# proto-small.net
KiCad netlist of a schematic drawn in EAGLE
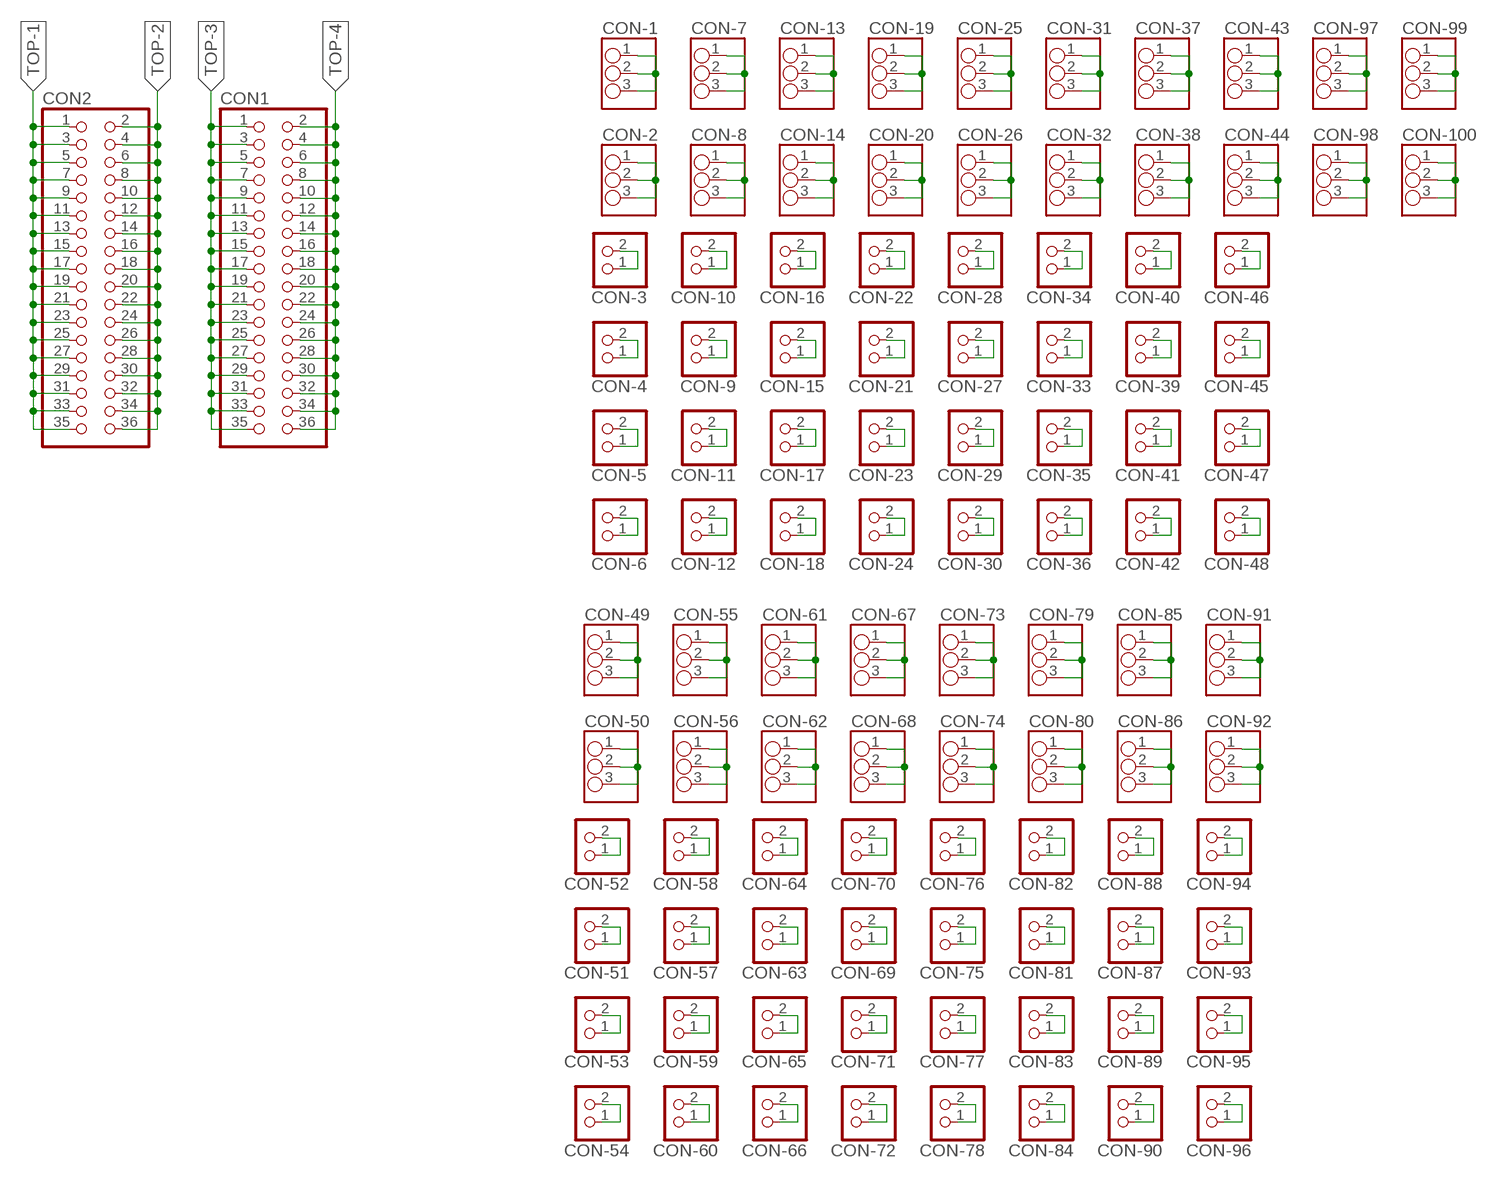
[diagram p0: schematic, sheet 1]

(export (version "E")
  (design (tool "Eeschema 10.0.6"))
  (components
    (comp (ref "CON-1")
      (value "GENERIC-1X3")
      (footprint "eagle-import:PINHEADER-100MIL-1X3-NOSILK")
      (libsource (lib "eagle-import") (part "GENERIC-1X3"))
    )
    (comp (ref "CON-2")
      (value "GENERIC-1X3")
      (footprint "eagle-import:PINHEADER-100MIL-1X3-NOSILK")
      (libsource (lib "eagle-import") (part "GENERIC-1X3"))
    )
    (comp (ref "CON-3")
      (value "GENERIC-1X2")
      (footprint "eagle-import:PINHEADER-100MIL-1X2-NOSILK")
      (libsource (lib "eagle-import") (part "GENERIC-1X2"))
    )
    (comp (ref "CON-4")
      (value "GENERIC-1X2")
      (footprint "eagle-import:PINHEADER-100MIL-1X2-NOSILK")
      (libsource (lib "eagle-import") (part "GENERIC-1X2"))
    )
    (comp (ref "CON-5")
      (value "GENERIC-1X2")
      (footprint "eagle-import:PINHEADER-100MIL-1X2-NOSILK")
      (libsource (lib "eagle-import") (part "GENERIC-1X2"))
    )
    (comp (ref "CON-6")
      (value "GENERIC-1X2")
      (footprint "eagle-import:PINHEADER-100MIL-1X2-NOSILK")
      (libsource (lib "eagle-import") (part "GENERIC-1X2"))
    )
    (comp (ref "CON-7")
      (value "GENERIC-1X3")
      (footprint "eagle-import:PINHEADER-100MIL-1X3-NOSILK")
      (libsource (lib "eagle-import") (part "GENERIC-1X3"))
    )
    (comp (ref "CON-8")
      (value "GENERIC-1X3")
      (footprint "eagle-import:PINHEADER-100MIL-1X3-NOSILK")
      (libsource (lib "eagle-import") (part "GENERIC-1X3"))
    )
    (comp (ref "CON-9")
      (value "GENERIC-1X2")
      (footprint "eagle-import:PINHEADER-100MIL-1X2-NOSILK")
      (libsource (lib "eagle-import") (part "GENERIC-1X2"))
    )
    (comp (ref "CON-10")
      (value "GENERIC-1X2")
      (footprint "eagle-import:PINHEADER-100MIL-1X2-NOSILK")
      (libsource (lib "eagle-import") (part "GENERIC-1X2"))
    )
    (comp (ref "CON-11")
      (value "GENERIC-1X2")
      (footprint "eagle-import:PINHEADER-100MIL-1X2-NOSILK")
      (libsource (lib "eagle-import") (part "GENERIC-1X2"))
    )
    (comp (ref "CON-12")
      (value "GENERIC-1X2")
      (footprint "eagle-import:PINHEADER-100MIL-1X2-NOSILK")
      (libsource (lib "eagle-import") (part "GENERIC-1X2"))
    )
    (comp (ref "CON-13")
      (value "GENERIC-1X3")
      (footprint "eagle-import:PINHEADER-100MIL-1X3-NOSILK")
      (libsource (lib "eagle-import") (part "GENERIC-1X3"))
    )
    (comp (ref "CON-14")
      (value "GENERIC-1X3")
      (footprint "eagle-import:PINHEADER-100MIL-1X3-NOSILK")
      (libsource (lib "eagle-import") (part "GENERIC-1X3"))
    )
    (comp (ref "CON-15")
      (value "GENERIC-1X2")
      (footprint "eagle-import:PINHEADER-100MIL-1X2-NOSILK")
      (libsource (lib "eagle-import") (part "GENERIC-1X2"))
    )
    (comp (ref "CON-16")
      (value "GENERIC-1X2")
      (footprint "eagle-import:PINHEADER-100MIL-1X2-NOSILK")
      (libsource (lib "eagle-import") (part "GENERIC-1X2"))
    )
    (comp (ref "CON-17")
      (value "GENERIC-1X2")
      (footprint "eagle-import:PINHEADER-100MIL-1X2-NOSILK")
      (libsource (lib "eagle-import") (part "GENERIC-1X2"))
    )
    (comp (ref "CON-18")
      (value "GENERIC-1X2")
      (footprint "eagle-import:PINHEADER-100MIL-1X2-NOSILK")
      (libsource (lib "eagle-import") (part "GENERIC-1X2"))
    )
    (comp (ref "CON-19")
      (value "GENERIC-1X3")
      (footprint "eagle-import:PINHEADER-100MIL-1X3-NOSILK")
      (libsource (lib "eagle-import") (part "GENERIC-1X3"))
    )
    (comp (ref "CON-20")
      (value "GENERIC-1X3")
      (footprint "eagle-import:PINHEADER-100MIL-1X3-NOSILK")
      (libsource (lib "eagle-import") (part "GENERIC-1X3"))
    )
    (comp (ref "CON-21")
      (value "GENERIC-1X2")
      (footprint "eagle-import:PINHEADER-100MIL-1X2-NOSILK")
      (libsource (lib "eagle-import") (part "GENERIC-1X2"))
    )
    (comp (ref "CON-22")
      (value "GENERIC-1X2")
      (footprint "eagle-import:PINHEADER-100MIL-1X2-NOSILK")
      (libsource (lib "eagle-import") (part "GENERIC-1X2"))
    )
    (comp (ref "CON-23")
      (value "GENERIC-1X2")
      (footprint "eagle-import:PINHEADER-100MIL-1X2-NOSILK")
      (libsource (lib "eagle-import") (part "GENERIC-1X2"))
    )
    (comp (ref "CON-24")
      (value "GENERIC-1X2")
      (footprint "eagle-import:PINHEADER-100MIL-1X2-NOSILK")
      (libsource (lib "eagle-import") (part "GENERIC-1X2"))
    )
    (comp (ref "CON-25")
      (value "GENERIC-1X3")
      (footprint "eagle-import:PINHEADER-100MIL-1X3-NOSILK")
      (libsource (lib "eagle-import") (part "GENERIC-1X3"))
    )
    (comp (ref "CON-26")
      (value "GENERIC-1X3")
      (footprint "eagle-import:PINHEADER-100MIL-1X3-NOSILK")
      (libsource (lib "eagle-import") (part "GENERIC-1X3"))
    )
    (comp (ref "CON-27")
      (value "GENERIC-1X2")
      (footprint "eagle-import:PINHEADER-100MIL-1X2-NOSILK")
      (libsource (lib "eagle-import") (part "GENERIC-1X2"))
    )
    (comp (ref "CON-28")
      (value "GENERIC-1X2")
      (footprint "eagle-import:PINHEADER-100MIL-1X2-NOSILK")
      (libsource (lib "eagle-import") (part "GENERIC-1X2"))
    )
    (comp (ref "CON-29")
      (value "GENERIC-1X2")
      (footprint "eagle-import:PINHEADER-100MIL-1X2-NOSILK")
      (libsource (lib "eagle-import") (part "GENERIC-1X2"))
    )
    (comp (ref "CON-30")
      (value "GENERIC-1X2")
      (footprint "eagle-import:PINHEADER-100MIL-1X2-NOSILK")
      (libsource (lib "eagle-import") (part "GENERIC-1X2"))
    )
    (comp (ref "CON-31")
      (value "GENERIC-1X3")
      (footprint "eagle-import:PINHEADER-100MIL-1X3-NOSILK")
      (libsource (lib "eagle-import") (part "GENERIC-1X3"))
    )
    (comp (ref "CON-32")
      (value "GENERIC-1X3")
      (footprint "eagle-import:PINHEADER-100MIL-1X3-NOSILK")
      (libsource (lib "eagle-import") (part "GENERIC-1X3"))
    )
    (comp (ref "CON-33")
      (value "GENERIC-1X2")
      (footprint "eagle-import:PINHEADER-100MIL-1X2-NOSILK")
      (libsource (lib "eagle-import") (part "GENERIC-1X2"))
    )
    (comp (ref "CON-34")
      (value "GENERIC-1X2")
      (footprint "eagle-import:PINHEADER-100MIL-1X2-NOSILK")
      (libsource (lib "eagle-import") (part "GENERIC-1X2"))
    )
    (comp (ref "CON-35")
      (value "GENERIC-1X2")
      (footprint "eagle-import:PINHEADER-100MIL-1X2-NOSILK")
      (libsource (lib "eagle-import") (part "GENERIC-1X2"))
    )
    (comp (ref "CON-36")
      (value "GENERIC-1X2")
      (footprint "eagle-import:PINHEADER-100MIL-1X2-NOSILK")
      (libsource (lib "eagle-import") (part "GENERIC-1X2"))
    )
    (comp (ref "CON-37")
      (value "GENERIC-1X3")
      (footprint "eagle-import:PINHEADER-100MIL-1X3-NOSILK")
      (libsource (lib "eagle-import") (part "GENERIC-1X3"))
    )
    (comp (ref "CON-38")
      (value "GENERIC-1X3")
      (footprint "eagle-import:PINHEADER-100MIL-1X3-NOSILK")
      (libsource (lib "eagle-import") (part "GENERIC-1X3"))
    )
    (comp (ref "CON-39")
      (value "GENERIC-1X2")
      (footprint "eagle-import:PINHEADER-100MIL-1X2-NOSILK")
      (libsource (lib "eagle-import") (part "GENERIC-1X2"))
    )
    (comp (ref "CON-40")
      (value "GENERIC-1X2")
      (footprint "eagle-import:PINHEADER-100MIL-1X2-NOSILK")
      (libsource (lib "eagle-import") (part "GENERIC-1X2"))
    )
    (comp (ref "CON-41")
      (value "GENERIC-1X2")
      (footprint "eagle-import:PINHEADER-100MIL-1X2-NOSILK")
      (libsource (lib "eagle-import") (part "GENERIC-1X2"))
    )
    (comp (ref "CON-42")
      (value "GENERIC-1X2")
      (footprint "eagle-import:PINHEADER-100MIL-1X2-NOSILK")
      (libsource (lib "eagle-import") (part "GENERIC-1X2"))
    )
    (comp (ref "CON-43")
      (value "GENERIC-1X3")
      (footprint "eagle-import:PINHEADER-100MIL-1X3-NOSILK")
      (libsource (lib "eagle-import") (part "GENERIC-1X3"))
    )
    (comp (ref "CON-44")
      (value "GENERIC-1X3")
      (footprint "eagle-import:PINHEADER-100MIL-1X3-NOSILK")
      (libsource (lib "eagle-import") (part "GENERIC-1X3"))
    )
    (comp (ref "CON-45")
      (value "GENERIC-1X2")
      (footprint "eagle-import:PINHEADER-100MIL-1X2-NOSILK")
      (libsource (lib "eagle-import") (part "GENERIC-1X2"))
    )
    (comp (ref "CON-46")
      (value "GENERIC-1X2")
      (footprint "eagle-import:PINHEADER-100MIL-1X2-NOSILK")
      (libsource (lib "eagle-import") (part "GENERIC-1X2"))
    )
    (comp (ref "CON-47")
      (value "GENERIC-1X2")
      (footprint "eagle-import:PINHEADER-100MIL-1X2-NOSILK")
      (libsource (lib "eagle-import") (part "GENERIC-1X2"))
    )
    (comp (ref "CON-48")
      (value "GENERIC-1X2")
      (footprint "eagle-import:PINHEADER-100MIL-1X2-NOSILK")
      (libsource (lib "eagle-import") (part "GENERIC-1X2"))
    )
    (comp (ref "CON-49")
      (value "GENERIC-1X3")
      (footprint "eagle-import:PINHEADER-100MIL-1X3-NOSILK")
      (libsource (lib "eagle-import") (part "GENERIC-1X3"))
    )
    (comp (ref "CON-50")
      (value "GENERIC-1X3")
      (footprint "eagle-import:PINHEADER-100MIL-1X3-NOSILK")
      (libsource (lib "eagle-import") (part "GENERIC-1X3"))
    )
    (comp (ref "CON-51")
      (value "GENERIC-1X2")
      (footprint "eagle-import:PINHEADER-100MIL-1X2-NOSILK")
      (libsource (lib "eagle-import") (part "GENERIC-1X2"))
    )
    (comp (ref "CON-52")
      (value "GENERIC-1X2")
      (footprint "eagle-import:PINHEADER-100MIL-1X2-NOSILK")
      (libsource (lib "eagle-import") (part "GENERIC-1X2"))
    )
    (comp (ref "CON-53")
      (value "GENERIC-1X2")
      (footprint "eagle-import:PINHEADER-100MIL-1X2-NOSILK")
      (libsource (lib "eagle-import") (part "GENERIC-1X2"))
    )
    (comp (ref "CON-54")
      (value "GENERIC-1X2")
      (footprint "eagle-import:PINHEADER-100MIL-1X2-NOSILK")
      (libsource (lib "eagle-import") (part "GENERIC-1X2"))
    )
    (comp (ref "CON-55")
      (value "GENERIC-1X3")
      (footprint "eagle-import:PINHEADER-100MIL-1X3-NOSILK")
      (libsource (lib "eagle-import") (part "GENERIC-1X3"))
    )
    (comp (ref "CON-56")
      (value "GENERIC-1X3")
      (footprint "eagle-import:PINHEADER-100MIL-1X3-NOSILK")
      (libsource (lib "eagle-import") (part "GENERIC-1X3"))
    )
    (comp (ref "CON-57")
      (value "GENERIC-1X2")
      (footprint "eagle-import:PINHEADER-100MIL-1X2-NOSILK")
      (libsource (lib "eagle-import") (part "GENERIC-1X2"))
    )
    (comp (ref "CON-58")
      (value "GENERIC-1X2")
      (footprint "eagle-import:PINHEADER-100MIL-1X2-NOSILK")
      (libsource (lib "eagle-import") (part "GENERIC-1X2"))
    )
    (comp (ref "CON-59")
      (value "GENERIC-1X2")
      (footprint "eagle-import:PINHEADER-100MIL-1X2-NOSILK")
      (libsource (lib "eagle-import") (part "GENERIC-1X2"))
    )
    (comp (ref "CON-60")
      (value "GENERIC-1X2")
      (footprint "eagle-import:PINHEADER-100MIL-1X2-NOSILK")
      (libsource (lib "eagle-import") (part "GENERIC-1X2"))
    )
    (comp (ref "CON-61")
      (value "GENERIC-1X3")
      (footprint "eagle-import:PINHEADER-100MIL-1X3-NOSILK")
      (libsource (lib "eagle-import") (part "GENERIC-1X3"))
    )
    (comp (ref "CON-62")
      (value "GENERIC-1X3")
      (footprint "eagle-import:PINHEADER-100MIL-1X3-NOSILK")
      (libsource (lib "eagle-import") (part "GENERIC-1X3"))
    )
    (comp (ref "CON-63")
      (value "GENERIC-1X2")
      (footprint "eagle-import:PINHEADER-100MIL-1X2-NOSILK")
      (libsource (lib "eagle-import") (part "GENERIC-1X2"))
    )
    (comp (ref "CON-64")
      (value "GENERIC-1X2")
      (footprint "eagle-import:PINHEADER-100MIL-1X2-NOSILK")
      (libsource (lib "eagle-import") (part "GENERIC-1X2"))
    )
    (comp (ref "CON-65")
      (value "GENERIC-1X2")
      (footprint "eagle-import:PINHEADER-100MIL-1X2-NOSILK")
      (libsource (lib "eagle-import") (part "GENERIC-1X2"))
    )
    (comp (ref "CON-66")
      (value "GENERIC-1X2")
      (footprint "eagle-import:PINHEADER-100MIL-1X2-NOSILK")
      (libsource (lib "eagle-import") (part "GENERIC-1X2"))
    )
    (comp (ref "CON-67")
      (value "GENERIC-1X3")
      (footprint "eagle-import:PINHEADER-100MIL-1X3-NOSILK")
      (libsource (lib "eagle-import") (part "GENERIC-1X3"))
    )
    (comp (ref "CON-68")
      (value "GENERIC-1X3")
      (footprint "eagle-import:PINHEADER-100MIL-1X3-NOSILK")
      (libsource (lib "eagle-import") (part "GENERIC-1X3"))
    )
    (comp (ref "CON-69")
      (value "GENERIC-1X2")
      (footprint "eagle-import:PINHEADER-100MIL-1X2-NOSILK")
      (libsource (lib "eagle-import") (part "GENERIC-1X2"))
    )
    (comp (ref "CON-70")
      (value "GENERIC-1X2")
      (footprint "eagle-import:PINHEADER-100MIL-1X2-NOSILK")
      (libsource (lib "eagle-import") (part "GENERIC-1X2"))
    )
    (comp (ref "CON-71")
      (value "GENERIC-1X2")
      (footprint "eagle-import:PINHEADER-100MIL-1X2-NOSILK")
      (libsource (lib "eagle-import") (part "GENERIC-1X2"))
    )
    (comp (ref "CON-72")
      (value "GENERIC-1X2")
      (footprint "eagle-import:PINHEADER-100MIL-1X2-NOSILK")
      (libsource (lib "eagle-import") (part "GENERIC-1X2"))
    )
    (comp (ref "CON-73")
      (value "GENERIC-1X3")
      (footprint "eagle-import:PINHEADER-100MIL-1X3-NOSILK")
      (libsource (lib "eagle-import") (part "GENERIC-1X3"))
    )
    (comp (ref "CON-74")
      (value "GENERIC-1X3")
      (footprint "eagle-import:PINHEADER-100MIL-1X3-NOSILK")
      (libsource (lib "eagle-import") (part "GENERIC-1X3"))
    )
    (comp (ref "CON-75")
      (value "GENERIC-1X2")
      (footprint "eagle-import:PINHEADER-100MIL-1X2-NOSILK")
      (libsource (lib "eagle-import") (part "GENERIC-1X2"))
    )
    (comp (ref "CON-76")
      (value "GENERIC-1X2")
      (footprint "eagle-import:PINHEADER-100MIL-1X2-NOSILK")
      (libsource (lib "eagle-import") (part "GENERIC-1X2"))
    )
    (comp (ref "CON-77")
      (value "GENERIC-1X2")
      (footprint "eagle-import:PINHEADER-100MIL-1X2-NOSILK")
      (libsource (lib "eagle-import") (part "GENERIC-1X2"))
    )
    (comp (ref "CON-78")
      (value "GENERIC-1X2")
      (footprint "eagle-import:PINHEADER-100MIL-1X2-NOSILK")
      (libsource (lib "eagle-import") (part "GENERIC-1X2"))
    )
    (comp (ref "CON-79")
      (value "GENERIC-1X3")
      (footprint "eagle-import:PINHEADER-100MIL-1X3-NOSILK")
      (libsource (lib "eagle-import") (part "GENERIC-1X3"))
    )
    (comp (ref "CON-80")
      (value "GENERIC-1X3")
      (footprint "eagle-import:PINHEADER-100MIL-1X3-NOSILK")
      (libsource (lib "eagle-import") (part "GENERIC-1X3"))
    )
    (comp (ref "CON-81")
      (value "GENERIC-1X2")
      (footprint "eagle-import:PINHEADER-100MIL-1X2-NOSILK")
      (libsource (lib "eagle-import") (part "GENERIC-1X2"))
    )
    (comp (ref "CON-82")
      (value "GENERIC-1X2")
      (footprint "eagle-import:PINHEADER-100MIL-1X2-NOSILK")
      (libsource (lib "eagle-import") (part "GENERIC-1X2"))
    )
    (comp (ref "CON-83")
      (value "GENERIC-1X2")
      (footprint "eagle-import:PINHEADER-100MIL-1X2-NOSILK")
      (libsource (lib "eagle-import") (part "GENERIC-1X2"))
    )
    (comp (ref "CON-84")
      (value "GENERIC-1X2")
      (footprint "eagle-import:PINHEADER-100MIL-1X2-NOSILK")
      (libsource (lib "eagle-import") (part "GENERIC-1X2"))
    )
    (comp (ref "CON-85")
      (value "GENERIC-1X3")
      (footprint "eagle-import:PINHEADER-100MIL-1X3-NOSILK")
      (libsource (lib "eagle-import") (part "GENERIC-1X3"))
    )
    (comp (ref "CON-86")
      (value "GENERIC-1X3")
      (footprint "eagle-import:PINHEADER-100MIL-1X3-NOSILK")
      (libsource (lib "eagle-import") (part "GENERIC-1X3"))
    )
    (comp (ref "CON-87")
      (value "GENERIC-1X2")
      (footprint "eagle-import:PINHEADER-100MIL-1X2-NOSILK")
      (libsource (lib "eagle-import") (part "GENERIC-1X2"))
    )
    (comp (ref "CON-88")
      (value "GENERIC-1X2")
      (footprint "eagle-import:PINHEADER-100MIL-1X2-NOSILK")
      (libsource (lib "eagle-import") (part "GENERIC-1X2"))
    )
    (comp (ref "CON-89")
      (value "GENERIC-1X2")
      (footprint "eagle-import:PINHEADER-100MIL-1X2-NOSILK")
      (libsource (lib "eagle-import") (part "GENERIC-1X2"))
    )
    (comp (ref "CON-90")
      (value "GENERIC-1X2")
      (footprint "eagle-import:PINHEADER-100MIL-1X2-NOSILK")
      (libsource (lib "eagle-import") (part "GENERIC-1X2"))
    )
    (comp (ref "CON-91")
      (value "GENERIC-1X3")
      (footprint "eagle-import:PINHEADER-100MIL-1X3-NOSILK")
      (libsource (lib "eagle-import") (part "GENERIC-1X3"))
    )
    (comp (ref "CON-92")
      (value "GENERIC-1X3")
      (footprint "eagle-import:PINHEADER-100MIL-1X3-NOSILK")
      (libsource (lib "eagle-import") (part "GENERIC-1X3"))
    )
    (comp (ref "CON-93")
      (value "GENERIC-1X2")
      (footprint "eagle-import:PINHEADER-100MIL-1X2-NOSILK")
      (libsource (lib "eagle-import") (part "GENERIC-1X2"))
    )
    (comp (ref "CON-94")
      (value "GENERIC-1X2")
      (footprint "eagle-import:PINHEADER-100MIL-1X2-NOSILK")
      (libsource (lib "eagle-import") (part "GENERIC-1X2"))
    )
    (comp (ref "CON-95")
      (value "GENERIC-1X2")
      (footprint "eagle-import:PINHEADER-100MIL-1X2-NOSILK")
      (libsource (lib "eagle-import") (part "GENERIC-1X2"))
    )
    (comp (ref "CON-96")
      (value "GENERIC-1X2")
      (footprint "eagle-import:PINHEADER-100MIL-1X2-NOSILK")
      (libsource (lib "eagle-import") (part "GENERIC-1X2"))
    )
    (comp (ref "CON-97")
      (value "GENERIC-1X3")
      (footprint "eagle-import:PINHEADER-100MIL-1X3-NOSILK")
      (libsource (lib "eagle-import") (part "GENERIC-1X3"))
    )
    (comp (ref "CON-98")
      (value "GENERIC-1X3")
      (footprint "eagle-import:PINHEADER-100MIL-1X3-NOSILK")
      (libsource (lib "eagle-import") (part "GENERIC-1X3"))
    )
    (comp (ref "CON-99")
      (value "GENERIC-1X3")
      (footprint "eagle-import:PINHEADER-100MIL-1X3-NOSILK")
      (libsource (lib "eagle-import") (part "GENERIC-1X3"))
    )
    (comp (ref "CON-100")
      (value "GENERIC-1X3")
      (footprint "eagle-import:PINHEADER-100MIL-1X3-NOSILK")
      (libsource (lib "eagle-import") (part "GENERIC-1X3"))
    )
    (comp (ref "CON1")
      (value "GENERIC-2X18")
      (footprint "eagle-import:PINHEADER-100MIL-2X18-NOSILK")
      (libsource (lib "eagle-import") (part "GENERIC-2X18"))
    )
    (comp (ref "CON2")
      (value "GENERIC-2X18")
      (footprint "eagle-import:PINHEADER-100MIL-2X18-NOSILK")
      (libsource (lib "eagle-import") (part "GENERIC-2X18"))
    )
  )
  (nets
    (net (code "1") (name "Net-(CON-1-Pad1)") (class "Default")
      (node (ref "CON-1") (pin "1") (pinfunction "1_1") (pintype "bidirectional"))
      (node (ref "CON-1") (pin "2") (pinfunction "2_2") (pintype "bidirectional"))
      (node (ref "CON-1") (pin "3") (pinfunction "3_3") (pintype "bidirectional"))
    )
    (net (code "2") (name "Net-(CON-2-Pad1)") (class "Default")
      (node (ref "CON-2") (pin "1") (pinfunction "1_1") (pintype "bidirectional"))
      (node (ref "CON-2") (pin "2") (pinfunction "2_2") (pintype "bidirectional"))
      (node (ref "CON-2") (pin "3") (pinfunction "3_3") (pintype "bidirectional"))
    )
    (net (code "3") (name "Net-(CON-3-Pad1)") (class "Default")
      (node (ref "CON-3") (pin "1") (pinfunction "1_1") (pintype "passive"))
      (node (ref "CON-3") (pin "2") (pinfunction "2_2") (pintype "passive"))
    )
    (net (code "4") (name "Net-(CON-4-Pad1)") (class "Default")
      (node (ref "CON-4") (pin "1") (pinfunction "1_1") (pintype "passive"))
      (node (ref "CON-4") (pin "2") (pinfunction "2_2") (pintype "passive"))
    )
    (net (code "5") (name "Net-(CON-5-Pad1)") (class "Default")
      (node (ref "CON-5") (pin "1") (pinfunction "1_1") (pintype "passive"))
      (node (ref "CON-5") (pin "2") (pinfunction "2_2") (pintype "passive"))
    )
    (net (code "6") (name "Net-(CON-6-Pad1)") (class "Default")
      (node (ref "CON-6") (pin "1") (pinfunction "1_1") (pintype "passive"))
      (node (ref "CON-6") (pin "2") (pinfunction "2_2") (pintype "passive"))
    )
    (net (code "7") (name "Net-(CON-7-Pad1)") (class "Default")
      (node (ref "CON-7") (pin "1") (pinfunction "1_1") (pintype "bidirectional"))
      (node (ref "CON-7") (pin "2") (pinfunction "2_2") (pintype "bidirectional"))
      (node (ref "CON-7") (pin "3") (pinfunction "3_3") (pintype "bidirectional"))
    )
    (net (code "8") (name "Net-(CON-8-Pad1)") (class "Default")
      (node (ref "CON-8") (pin "1") (pinfunction "1_1") (pintype "bidirectional"))
      (node (ref "CON-8") (pin "2") (pinfunction "2_2") (pintype "bidirectional"))
      (node (ref "CON-8") (pin "3") (pinfunction "3_3") (pintype "bidirectional"))
    )
    (net (code "9") (name "Net-(CON-9-Pad1)") (class "Default")
      (node (ref "CON-9") (pin "1") (pinfunction "1_1") (pintype "passive"))
      (node (ref "CON-9") (pin "2") (pinfunction "2_2") (pintype "passive"))
    )
    (net (code "10") (name "Net-(CON-10-Pad1)") (class "Default")
      (node (ref "CON-10") (pin "1") (pinfunction "1_1") (pintype "passive"))
      (node (ref "CON-10") (pin "2") (pinfunction "2_2") (pintype "passive"))
    )
    (net (code "11") (name "Net-(CON-11-Pad1)") (class "Default")
      (node (ref "CON-11") (pin "1") (pinfunction "1_1") (pintype "passive"))
      (node (ref "CON-11") (pin "2") (pinfunction "2_2") (pintype "passive"))
    )
    (net (code "12") (name "Net-(CON-12-Pad1)") (class "Default")
      (node (ref "CON-12") (pin "1") (pinfunction "1_1") (pintype "passive"))
      (node (ref "CON-12") (pin "2") (pinfunction "2_2") (pintype "passive"))
    )
    (net (code "13") (name "Net-(CON-13-Pad1)") (class "Default")
      (node (ref "CON-13") (pin "1") (pinfunction "1_1") (pintype "bidirectional"))
      (node (ref "CON-13") (pin "2") (pinfunction "2_2") (pintype "bidirectional"))
      (node (ref "CON-13") (pin "3") (pinfunction "3_3") (pintype "bidirectional"))
    )
    (net (code "14") (name "Net-(CON-14-Pad1)") (class "Default")
      (node (ref "CON-14") (pin "1") (pinfunction "1_1") (pintype "bidirectional"))
      (node (ref "CON-14") (pin "2") (pinfunction "2_2") (pintype "bidirectional"))
      (node (ref "CON-14") (pin "3") (pinfunction "3_3") (pintype "bidirectional"))
    )
    (net (code "15") (name "Net-(CON-15-Pad1)") (class "Default")
      (node (ref "CON-15") (pin "1") (pinfunction "1_1") (pintype "passive"))
      (node (ref "CON-15") (pin "2") (pinfunction "2_2") (pintype "passive"))
    )
    (net (code "16") (name "Net-(CON-16-Pad1)") (class "Default")
      (node (ref "CON-16") (pin "1") (pinfunction "1_1") (pintype "passive"))
      (node (ref "CON-16") (pin "2") (pinfunction "2_2") (pintype "passive"))
    )
    (net (code "17") (name "Net-(CON-17-Pad1)") (class "Default")
      (node (ref "CON-17") (pin "1") (pinfunction "1_1") (pintype "passive"))
      (node (ref "CON-17") (pin "2") (pinfunction "2_2") (pintype "passive"))
    )
    (net (code "18") (name "Net-(CON-18-Pad1)") (class "Default")
      (node (ref "CON-18") (pin "1") (pinfunction "1_1") (pintype "passive"))
      (node (ref "CON-18") (pin "2") (pinfunction "2_2") (pintype "passive"))
    )
    (net (code "19") (name "Net-(CON-19-Pad1)") (class "Default")
      (node (ref "CON-19") (pin "1") (pinfunction "1_1") (pintype "bidirectional"))
      (node (ref "CON-19") (pin "2") (pinfunction "2_2") (pintype "bidirectional"))
      (node (ref "CON-19") (pin "3") (pinfunction "3_3") (pintype "bidirectional"))
    )
    (net (code "20") (name "Net-(CON-20-Pad1)") (class "Default")
      (node (ref "CON-20") (pin "1") (pinfunction "1_1") (pintype "bidirectional"))
      (node (ref "CON-20") (pin "2") (pinfunction "2_2") (pintype "bidirectional"))
      (node (ref "CON-20") (pin "3") (pinfunction "3_3") (pintype "bidirectional"))
    )
    (net (code "21") (name "Net-(CON-21-Pad1)") (class "Default")
      (node (ref "CON-21") (pin "1") (pinfunction "1_1") (pintype "passive"))
      (node (ref "CON-21") (pin "2") (pinfunction "2_2") (pintype "passive"))
    )
    (net (code "22") (name "Net-(CON-22-Pad1)") (class "Default")
      (node (ref "CON-22") (pin "1") (pinfunction "1_1") (pintype "passive"))
      (node (ref "CON-22") (pin "2") (pinfunction "2_2") (pintype "passive"))
    )
    (net (code "23") (name "Net-(CON-23-Pad1)") (class "Default")
      (node (ref "CON-23") (pin "1") (pinfunction "1_1") (pintype "passive"))
      (node (ref "CON-23") (pin "2") (pinfunction "2_2") (pintype "passive"))
    )
    (net (code "24") (name "Net-(CON-24-Pad1)") (class "Default")
      (node (ref "CON-24") (pin "1") (pinfunction "1_1") (pintype "passive"))
      (node (ref "CON-24") (pin "2") (pinfunction "2_2") (pintype "passive"))
    )
    (net (code "25") (name "Net-(CON-25-Pad1)") (class "Default")
      (node (ref "CON-25") (pin "1") (pinfunction "1_1") (pintype "bidirectional"))
      (node (ref "CON-25") (pin "2") (pinfunction "2_2") (pintype "bidirectional"))
      (node (ref "CON-25") (pin "3") (pinfunction "3_3") (pintype "bidirectional"))
    )
    (net (code "26") (name "Net-(CON-26-Pad1)") (class "Default")
      (node (ref "CON-26") (pin "1") (pinfunction "1_1") (pintype "bidirectional"))
      (node (ref "CON-26") (pin "2") (pinfunction "2_2") (pintype "bidirectional"))
      (node (ref "CON-26") (pin "3") (pinfunction "3_3") (pintype "bidirectional"))
    )
    (net (code "27") (name "Net-(CON-27-Pad1)") (class "Default")
      (node (ref "CON-27") (pin "1") (pinfunction "1_1") (pintype "passive"))
      (node (ref "CON-27") (pin "2") (pinfunction "2_2") (pintype "passive"))
    )
    (net (code "28") (name "Net-(CON-28-Pad1)") (class "Default")
      (node (ref "CON-28") (pin "1") (pinfunction "1_1") (pintype "passive"))
      (node (ref "CON-28") (pin "2") (pinfunction "2_2") (pintype "passive"))
    )
    (net (code "29") (name "Net-(CON-29-Pad1)") (class "Default")
      (node (ref "CON-29") (pin "1") (pinfunction "1_1") (pintype "passive"))
      (node (ref "CON-29") (pin "2") (pinfunction "2_2") (pintype "passive"))
    )
    (net (code "30") (name "Net-(CON-30-Pad1)") (class "Default")
      (node (ref "CON-30") (pin "1") (pinfunction "1_1") (pintype "passive"))
      (node (ref "CON-30") (pin "2") (pinfunction "2_2") (pintype "passive"))
    )
    (net (code "31") (name "Net-(CON-31-Pad1)") (class "Default")
      (node (ref "CON-31") (pin "1") (pinfunction "1_1") (pintype "bidirectional"))
      (node (ref "CON-31") (pin "2") (pinfunction "2_2") (pintype "bidirectional"))
      (node (ref "CON-31") (pin "3") (pinfunction "3_3") (pintype "bidirectional"))
    )
    (net (code "32") (name "Net-(CON-32-Pad1)") (class "Default")
      (node (ref "CON-32") (pin "1") (pinfunction "1_1") (pintype "bidirectional"))
      (node (ref "CON-32") (pin "2") (pinfunction "2_2") (pintype "bidirectional"))
      (node (ref "CON-32") (pin "3") (pinfunction "3_3") (pintype "bidirectional"))
    )
    (net (code "33") (name "Net-(CON-33-Pad1)") (class "Default")
      (node (ref "CON-33") (pin "1") (pinfunction "1_1") (pintype "passive"))
      (node (ref "CON-33") (pin "2") (pinfunction "2_2") (pintype "passive"))
    )
    (net (code "34") (name "Net-(CON-34-Pad1)") (class "Default")
      (node (ref "CON-34") (pin "1") (pinfunction "1_1") (pintype "passive"))
      (node (ref "CON-34") (pin "2") (pinfunction "2_2") (pintype "passive"))
    )
    (net (code "35") (name "Net-(CON-35-Pad1)") (class "Default")
      (node (ref "CON-35") (pin "1") (pinfunction "1_1") (pintype "passive"))
      (node (ref "CON-35") (pin "2") (pinfunction "2_2") (pintype "passive"))
    )
    (net (code "36") (name "Net-(CON-36-Pad1)") (class "Default")
      (node (ref "CON-36") (pin "1") (pinfunction "1_1") (pintype "passive"))
      (node (ref "CON-36") (pin "2") (pinfunction "2_2") (pintype "passive"))
    )
    (net (code "37") (name "Net-(CON-37-Pad1)") (class "Default")
      (node (ref "CON-37") (pin "1") (pinfunction "1_1") (pintype "bidirectional"))
      (node (ref "CON-37") (pin "2") (pinfunction "2_2") (pintype "bidirectional"))
      (node (ref "CON-37") (pin "3") (pinfunction "3_3") (pintype "bidirectional"))
    )
    (net (code "38") (name "Net-(CON-38-Pad1)") (class "Default")
      (node (ref "CON-38") (pin "1") (pinfunction "1_1") (pintype "bidirectional"))
      (node (ref "CON-38") (pin "2") (pinfunction "2_2") (pintype "bidirectional"))
      (node (ref "CON-38") (pin "3") (pinfunction "3_3") (pintype "bidirectional"))
    )
    (net (code "39") (name "Net-(CON-39-Pad1)") (class "Default")
      (node (ref "CON-39") (pin "1") (pinfunction "1_1") (pintype "passive"))
      (node (ref "CON-39") (pin "2") (pinfunction "2_2") (pintype "passive"))
    )
    (net (code "40") (name "Net-(CON-40-Pad1)") (class "Default")
      (node (ref "CON-40") (pin "1") (pinfunction "1_1") (pintype "passive"))
      (node (ref "CON-40") (pin "2") (pinfunction "2_2") (pintype "passive"))
    )
    (net (code "41") (name "Net-(CON-41-Pad1)") (class "Default")
      (node (ref "CON-41") (pin "1") (pinfunction "1_1") (pintype "passive"))
      (node (ref "CON-41") (pin "2") (pinfunction "2_2") (pintype "passive"))
    )
    (net (code "42") (name "Net-(CON-42-Pad1)") (class "Default")
      (node (ref "CON-42") (pin "1") (pinfunction "1_1") (pintype "passive"))
      (node (ref "CON-42") (pin "2") (pinfunction "2_2") (pintype "passive"))
    )
    (net (code "43") (name "Net-(CON-43-Pad1)") (class "Default")
      (node (ref "CON-43") (pin "1") (pinfunction "1_1") (pintype "bidirectional"))
      (node (ref "CON-43") (pin "2") (pinfunction "2_2") (pintype "bidirectional"))
      (node (ref "CON-43") (pin "3") (pinfunction "3_3") (pintype "bidirectional"))
    )
    (net (code "44") (name "Net-(CON-44-Pad1)") (class "Default")
      (node (ref "CON-44") (pin "1") (pinfunction "1_1") (pintype "bidirectional"))
      (node (ref "CON-44") (pin "2") (pinfunction "2_2") (pintype "bidirectional"))
      (node (ref "CON-44") (pin "3") (pinfunction "3_3") (pintype "bidirectional"))
    )
    (net (code "45") (name "Net-(CON-45-Pad1)") (class "Default")
      (node (ref "CON-45") (pin "1") (pinfunction "1_1") (pintype "passive"))
      (node (ref "CON-45") (pin "2") (pinfunction "2_2") (pintype "passive"))
    )
    (net (code "46") (name "Net-(CON-46-Pad1)") (class "Default")
      (node (ref "CON-46") (pin "1") (pinfunction "1_1") (pintype "passive"))
      (node (ref "CON-46") (pin "2") (pinfunction "2_2") (pintype "passive"))
    )
    (net (code "47") (name "Net-(CON-47-Pad1)") (class "Default")
      (node (ref "CON-47") (pin "1") (pinfunction "1_1") (pintype "passive"))
      (node (ref "CON-47") (pin "2") (pinfunction "2_2") (pintype "passive"))
    )
    (net (code "48") (name "Net-(CON-48-Pad1)") (class "Default")
      (node (ref "CON-48") (pin "1") (pinfunction "1_1") (pintype "passive"))
      (node (ref "CON-48") (pin "2") (pinfunction "2_2") (pintype "passive"))
    )
    (net (code "49") (name "Net-(CON-49-Pad1)") (class "Default")
      (node (ref "CON-49") (pin "1") (pinfunction "1_1") (pintype "bidirectional"))
      (node (ref "CON-49") (pin "2") (pinfunction "2_2") (pintype "bidirectional"))
      (node (ref "CON-49") (pin "3") (pinfunction "3_3") (pintype "bidirectional"))
    )
    (net (code "50") (name "Net-(CON-50-Pad1)") (class "Default")
      (node (ref "CON-50") (pin "1") (pinfunction "1_1") (pintype "bidirectional"))
      (node (ref "CON-50") (pin "2") (pinfunction "2_2") (pintype "bidirectional"))
      (node (ref "CON-50") (pin "3") (pinfunction "3_3") (pintype "bidirectional"))
    )
    (net (code "51") (name "Net-(CON-51-Pad1)") (class "Default")
      (node (ref "CON-51") (pin "1") (pinfunction "1_1") (pintype "passive"))
      (node (ref "CON-51") (pin "2") (pinfunction "2_2") (pintype "passive"))
    )
    (net (code "52") (name "Net-(CON-52-Pad1)") (class "Default")
      (node (ref "CON-52") (pin "1") (pinfunction "1_1") (pintype "passive"))
      (node (ref "CON-52") (pin "2") (pinfunction "2_2") (pintype "passive"))
    )
    (net (code "53") (name "Net-(CON-53-Pad1)") (class "Default")
      (node (ref "CON-53") (pin "1") (pinfunction "1_1") (pintype "passive"))
      (node (ref "CON-53") (pin "2") (pinfunction "2_2") (pintype "passive"))
    )
    (net (code "54") (name "Net-(CON-54-Pad1)") (class "Default")
      (node (ref "CON-54") (pin "1") (pinfunction "1_1") (pintype "passive"))
      (node (ref "CON-54") (pin "2") (pinfunction "2_2") (pintype "passive"))
    )
    (net (code "55") (name "Net-(CON-55-Pad1)") (class "Default")
      (node (ref "CON-55") (pin "1") (pinfunction "1_1") (pintype "bidirectional"))
      (node (ref "CON-55") (pin "2") (pinfunction "2_2") (pintype "bidirectional"))
      (node (ref "CON-55") (pin "3") (pinfunction "3_3") (pintype "bidirectional"))
    )
    (net (code "56") (name "Net-(CON-56-Pad1)") (class "Default")
      (node (ref "CON-56") (pin "1") (pinfunction "1_1") (pintype "bidirectional"))
      (node (ref "CON-56") (pin "2") (pinfunction "2_2") (pintype "bidirectional"))
      (node (ref "CON-56") (pin "3") (pinfunction "3_3") (pintype "bidirectional"))
    )
    (net (code "57") (name "Net-(CON-57-Pad1)") (class "Default")
      (node (ref "CON-57") (pin "1") (pinfunction "1_1") (pintype "passive"))
      (node (ref "CON-57") (pin "2") (pinfunction "2_2") (pintype "passive"))
    )
    (net (code "58") (name "Net-(CON-58-Pad1)") (class "Default")
      (node (ref "CON-58") (pin "1") (pinfunction "1_1") (pintype "passive"))
      (node (ref "CON-58") (pin "2") (pinfunction "2_2") (pintype "passive"))
    )
    (net (code "59") (name "Net-(CON-59-Pad1)") (class "Default")
      (node (ref "CON-59") (pin "1") (pinfunction "1_1") (pintype "passive"))
      (node (ref "CON-59") (pin "2") (pinfunction "2_2") (pintype "passive"))
    )
    (net (code "60") (name "Net-(CON-60-Pad1)") (class "Default")
      (node (ref "CON-60") (pin "1") (pinfunction "1_1") (pintype "passive"))
      (node (ref "CON-60") (pin "2") (pinfunction "2_2") (pintype "passive"))
    )
    (net (code "61") (name "Net-(CON-61-Pad1)") (class "Default")
      (node (ref "CON-61") (pin "1") (pinfunction "1_1") (pintype "bidirectional"))
      (node (ref "CON-61") (pin "2") (pinfunction "2_2") (pintype "bidirectional"))
      (node (ref "CON-61") (pin "3") (pinfunction "3_3") (pintype "bidirectional"))
    )
    (net (code "62") (name "Net-(CON-62-Pad1)") (class "Default")
      (node (ref "CON-62") (pin "1") (pinfunction "1_1") (pintype "bidirectional"))
      (node (ref "CON-62") (pin "2") (pinfunction "2_2") (pintype "bidirectional"))
      (node (ref "CON-62") (pin "3") (pinfunction "3_3") (pintype "bidirectional"))
    )
    (net (code "63") (name "Net-(CON-63-Pad1)") (class "Default")
      (node (ref "CON-63") (pin "1") (pinfunction "1_1") (pintype "passive"))
      (node (ref "CON-63") (pin "2") (pinfunction "2_2") (pintype "passive"))
    )
    (net (code "64") (name "Net-(CON-64-Pad1)") (class "Default")
      (node (ref "CON-64") (pin "1") (pinfunction "1_1") (pintype "passive"))
      (node (ref "CON-64") (pin "2") (pinfunction "2_2") (pintype "passive"))
    )
    (net (code "65") (name "Net-(CON-65-Pad1)") (class "Default")
      (node (ref "CON-65") (pin "1") (pinfunction "1_1") (pintype "passive"))
      (node (ref "CON-65") (pin "2") (pinfunction "2_2") (pintype "passive"))
    )
    (net (code "66") (name "Net-(CON-66-Pad1)") (class "Default")
      (node (ref "CON-66") (pin "1") (pinfunction "1_1") (pintype "passive"))
      (node (ref "CON-66") (pin "2") (pinfunction "2_2") (pintype "passive"))
    )
    (net (code "67") (name "Net-(CON-67-Pad1)") (class "Default")
      (node (ref "CON-67") (pin "1") (pinfunction "1_1") (pintype "bidirectional"))
      (node (ref "CON-67") (pin "2") (pinfunction "2_2") (pintype "bidirectional"))
      (node (ref "CON-67") (pin "3") (pinfunction "3_3") (pintype "bidirectional"))
    )
    (net (code "68") (name "Net-(CON-68-Pad1)") (class "Default")
      (node (ref "CON-68") (pin "1") (pinfunction "1_1") (pintype "bidirectional"))
      (node (ref "CON-68") (pin "2") (pinfunction "2_2") (pintype "bidirectional"))
      (node (ref "CON-68") (pin "3") (pinfunction "3_3") (pintype "bidirectional"))
    )
    (net (code "69") (name "Net-(CON-69-Pad1)") (class "Default")
      (node (ref "CON-69") (pin "1") (pinfunction "1_1") (pintype "passive"))
      (node (ref "CON-69") (pin "2") (pinfunction "2_2") (pintype "passive"))
    )
    (net (code "70") (name "Net-(CON-70-Pad1)") (class "Default")
      (node (ref "CON-70") (pin "1") (pinfunction "1_1") (pintype "passive"))
      (node (ref "CON-70") (pin "2") (pinfunction "2_2") (pintype "passive"))
    )
    (net (code "71") (name "Net-(CON-71-Pad1)") (class "Default")
      (node (ref "CON-71") (pin "1") (pinfunction "1_1") (pintype "passive"))
      (node (ref "CON-71") (pin "2") (pinfunction "2_2") (pintype "passive"))
    )
    (net (code "72") (name "Net-(CON-72-Pad1)") (class "Default")
      (node (ref "CON-72") (pin "1") (pinfunction "1_1") (pintype "passive"))
      (node (ref "CON-72") (pin "2") (pinfunction "2_2") (pintype "passive"))
    )
    (net (code "73") (name "Net-(CON-73-Pad1)") (class "Default")
      (node (ref "CON-73") (pin "1") (pinfunction "1_1") (pintype "bidirectional"))
      (node (ref "CON-73") (pin "2") (pinfunction "2_2") (pintype "bidirectional"))
      (node (ref "CON-73") (pin "3") (pinfunction "3_3") (pintype "bidirectional"))
    )
    (net (code "74") (name "Net-(CON-74-Pad1)") (class "Default")
      (node (ref "CON-74") (pin "1") (pinfunction "1_1") (pintype "bidirectional"))
      (node (ref "CON-74") (pin "2") (pinfunction "2_2") (pintype "bidirectional"))
      (node (ref "CON-74") (pin "3") (pinfunction "3_3") (pintype "bidirectional"))
    )
    (net (code "75") (name "Net-(CON-75-Pad1)") (class "Default")
      (node (ref "CON-75") (pin "1") (pinfunction "1_1") (pintype "passive"))
      (node (ref "CON-75") (pin "2") (pinfunction "2_2") (pintype "passive"))
    )
    (net (code "76") (name "Net-(CON-76-Pad1)") (class "Default")
      (node (ref "CON-76") (pin "1") (pinfunction "1_1") (pintype "passive"))
      (node (ref "CON-76") (pin "2") (pinfunction "2_2") (pintype "passive"))
    )
    (net (code "77") (name "Net-(CON-77-Pad1)") (class "Default")
      (node (ref "CON-77") (pin "1") (pinfunction "1_1") (pintype "passive"))
      (node (ref "CON-77") (pin "2") (pinfunction "2_2") (pintype "passive"))
    )
    (net (code "78") (name "Net-(CON-78-Pad1)") (class "Default")
      (node (ref "CON-78") (pin "1") (pinfunction "1_1") (pintype "passive"))
      (node (ref "CON-78") (pin "2") (pinfunction "2_2") (pintype "passive"))
    )
    (net (code "79") (name "Net-(CON-79-Pad1)") (class "Default")
      (node (ref "CON-79") (pin "1") (pinfunction "1_1") (pintype "bidirectional"))
      (node (ref "CON-79") (pin "2") (pinfunction "2_2") (pintype "bidirectional"))
      (node (ref "CON-79") (pin "3") (pinfunction "3_3") (pintype "bidirectional"))
    )
    (net (code "80") (name "Net-(CON-80-Pad1)") (class "Default")
      (node (ref "CON-80") (pin "1") (pinfunction "1_1") (pintype "bidirectional"))
      (node (ref "CON-80") (pin "2") (pinfunction "2_2") (pintype "bidirectional"))
      (node (ref "CON-80") (pin "3") (pinfunction "3_3") (pintype "bidirectional"))
    )
    (net (code "81") (name "Net-(CON-81-Pad1)") (class "Default")
      (node (ref "CON-81") (pin "1") (pinfunction "1_1") (pintype "passive"))
      (node (ref "CON-81") (pin "2") (pinfunction "2_2") (pintype "passive"))
    )
    (net (code "82") (name "Net-(CON-82-Pad1)") (class "Default")
      (node (ref "CON-82") (pin "1") (pinfunction "1_1") (pintype "passive"))
      (node (ref "CON-82") (pin "2") (pinfunction "2_2") (pintype "passive"))
    )
    (net (code "83") (name "Net-(CON-83-Pad1)") (class "Default")
      (node (ref "CON-83") (pin "1") (pinfunction "1_1") (pintype "passive"))
      (node (ref "CON-83") (pin "2") (pinfunction "2_2") (pintype "passive"))
    )
    (net (code "84") (name "Net-(CON-84-Pad1)") (class "Default")
      (node (ref "CON-84") (pin "1") (pinfunction "1_1") (pintype "passive"))
      (node (ref "CON-84") (pin "2") (pinfunction "2_2") (pintype "passive"))
    )
    (net (code "85") (name "Net-(CON-85-Pad1)") (class "Default")
      (node (ref "CON-85") (pin "1") (pinfunction "1_1") (pintype "bidirectional"))
      (node (ref "CON-85") (pin "2") (pinfunction "2_2") (pintype "bidirectional"))
      (node (ref "CON-85") (pin "3") (pinfunction "3_3") (pintype "bidirectional"))
    )
    (net (code "86") (name "Net-(CON-86-Pad1)") (class "Default")
      (node (ref "CON-86") (pin "1") (pinfunction "1_1") (pintype "bidirectional"))
      (node (ref "CON-86") (pin "2") (pinfunction "2_2") (pintype "bidirectional"))
      (node (ref "CON-86") (pin "3") (pinfunction "3_3") (pintype "bidirectional"))
    )
    (net (code "87") (name "Net-(CON-87-Pad1)") (class "Default")
      (node (ref "CON-87") (pin "1") (pinfunction "1_1") (pintype "passive"))
      (node (ref "CON-87") (pin "2") (pinfunction "2_2") (pintype "passive"))
    )
    (net (code "88") (name "Net-(CON-88-Pad1)") (class "Default")
      (node (ref "CON-88") (pin "1") (pinfunction "1_1") (pintype "passive"))
      (node (ref "CON-88") (pin "2") (pinfunction "2_2") (pintype "passive"))
    )
    (net (code "89") (name "Net-(CON-89-Pad1)") (class "Default")
      (node (ref "CON-89") (pin "1") (pinfunction "1_1") (pintype "passive"))
      (node (ref "CON-89") (pin "2") (pinfunction "2_2") (pintype "passive"))
    )
    (net (code "90") (name "Net-(CON-90-Pad1)") (class "Default")
      (node (ref "CON-90") (pin "1") (pinfunction "1_1") (pintype "passive"))
      (node (ref "CON-90") (pin "2") (pinfunction "2_2") (pintype "passive"))
    )
    (net (code "91") (name "Net-(CON-91-Pad1)") (class "Default")
      (node (ref "CON-91") (pin "1") (pinfunction "1_1") (pintype "bidirectional"))
      (node (ref "CON-91") (pin "2") (pinfunction "2_2") (pintype "bidirectional"))
      (node (ref "CON-91") (pin "3") (pinfunction "3_3") (pintype "bidirectional"))
    )
    (net (code "92") (name "Net-(CON-92-Pad1)") (class "Default")
      (node (ref "CON-92") (pin "1") (pinfunction "1_1") (pintype "bidirectional"))
      (node (ref "CON-92") (pin "2") (pinfunction "2_2") (pintype "bidirectional"))
      (node (ref "CON-92") (pin "3") (pinfunction "3_3") (pintype "bidirectional"))
    )
    (net (code "93") (name "Net-(CON-93-Pad1)") (class "Default")
      (node (ref "CON-93") (pin "1") (pinfunction "1_1") (pintype "passive"))
      (node (ref "CON-93") (pin "2") (pinfunction "2_2") (pintype "passive"))
    )
    (net (code "94") (name "Net-(CON-94-Pad1)") (class "Default")
      (node (ref "CON-94") (pin "1") (pinfunction "1_1") (pintype "passive"))
      (node (ref "CON-94") (pin "2") (pinfunction "2_2") (pintype "passive"))
    )
    (net (code "95") (name "Net-(CON-95-Pad1)") (class "Default")
      (node (ref "CON-95") (pin "1") (pinfunction "1_1") (pintype "passive"))
      (node (ref "CON-95") (pin "2") (pinfunction "2_2") (pintype "passive"))
    )
    (net (code "96") (name "Net-(CON-96-Pad1)") (class "Default")
      (node (ref "CON-96") (pin "1") (pinfunction "1_1") (pintype "passive"))
      (node (ref "CON-96") (pin "2") (pinfunction "2_2") (pintype "passive"))
    )
    (net (code "97") (name "Net-(CON-97-Pad1)") (class "Default")
      (node (ref "CON-97") (pin "1") (pinfunction "1_1") (pintype "bidirectional"))
      (node (ref "CON-97") (pin "2") (pinfunction "2_2") (pintype "bidirectional"))
      (node (ref "CON-97") (pin "3") (pinfunction "3_3") (pintype "bidirectional"))
    )
    (net (code "98") (name "Net-(CON-98-Pad1)") (class "Default")
      (node (ref "CON-98") (pin "1") (pinfunction "1_1") (pintype "bidirectional"))
      (node (ref "CON-98") (pin "2") (pinfunction "2_2") (pintype "bidirectional"))
      (node (ref "CON-98") (pin "3") (pinfunction "3_3") (pintype "bidirectional"))
    )
    (net (code "99") (name "Net-(CON-99-Pad1)") (class "Default")
      (node (ref "CON-99") (pin "1") (pinfunction "1_1") (pintype "bidirectional"))
      (node (ref "CON-99") (pin "2") (pinfunction "2_2") (pintype "bidirectional"))
      (node (ref "CON-99") (pin "3") (pinfunction "3_3") (pintype "bidirectional"))
    )
    (net (code "100") (name "Net-(CON-100-Pad1)") (class "Default")
      (node (ref "CON-100") (pin "1") (pinfunction "1_1") (pintype "bidirectional"))
      (node (ref "CON-100") (pin "2") (pinfunction "2_2") (pintype "bidirectional"))
      (node (ref "CON-100") (pin "3") (pinfunction "3_3") (pintype "bidirectional"))
    )
    (net (code "101") (name "TOP-1") (class "Default")
      (node (ref "CON2") (pin "1") (pinfunction "1_1") (pintype "passive"))
      (node (ref "CON2") (pin "11") (pinfunction "11_11") (pintype "passive"))
      (node (ref "CON2") (pin "13") (pinfunction "13_13") (pintype "passive"))
      (node (ref "CON2") (pin "15") (pinfunction "15_15") (pintype "passive"))
      (node (ref "CON2") (pin "17") (pinfunction "17_17") (pintype "passive"))
      (node (ref "CON2") (pin "19") (pinfunction "19_19") (pintype "passive"))
      (node (ref "CON2") (pin "21") (pinfunction "21_21") (pintype "passive"))
      (node (ref "CON2") (pin "23") (pinfunction "23_23") (pintype "passive"))
      (node (ref "CON2") (pin "25") (pinfunction "25_25") (pintype "passive"))
      (node (ref "CON2") (pin "27") (pinfunction "27_27") (pintype "passive"))
      (node (ref "CON2") (pin "29") (pinfunction "29_29") (pintype "passive"))
      (node (ref "CON2") (pin "3") (pinfunction "3_3") (pintype "passive"))
      (node (ref "CON2") (pin "31") (pinfunction "31_31") (pintype "passive"))
      (node (ref "CON2") (pin "33") (pinfunction "33_33") (pintype "passive"))
      (node (ref "CON2") (pin "35") (pinfunction "35_35") (pintype "passive"))
      (node (ref "CON2") (pin "5") (pinfunction "5_5") (pintype "passive"))
      (node (ref "CON2") (pin "7") (pinfunction "7_7") (pintype "passive"))
      (node (ref "CON2") (pin "9") (pinfunction "9_9") (pintype "passive"))
    )
    (net (code "102") (name "TOP-2") (class "Default")
      (node (ref "CON2") (pin "10") (pinfunction "10_10") (pintype "passive"))
      (node (ref "CON2") (pin "12") (pinfunction "12_12") (pintype "passive"))
      (node (ref "CON2") (pin "14") (pinfunction "14_14") (pintype "passive"))
      (node (ref "CON2") (pin "16") (pinfunction "16_16") (pintype "passive"))
      (node (ref "CON2") (pin "18") (pinfunction "18_18") (pintype "passive"))
      (node (ref "CON2") (pin "2") (pinfunction "2_2") (pintype "passive"))
      (node (ref "CON2") (pin "20") (pinfunction "20_20") (pintype "passive"))
      (node (ref "CON2") (pin "22") (pinfunction "22_22") (pintype "passive"))
      (node (ref "CON2") (pin "24") (pinfunction "24_24") (pintype "passive"))
      (node (ref "CON2") (pin "26") (pinfunction "26_26") (pintype "passive"))
      (node (ref "CON2") (pin "28") (pinfunction "28_28") (pintype "passive"))
      (node (ref "CON2") (pin "30") (pinfunction "30_30") (pintype "passive"))
      (node (ref "CON2") (pin "32") (pinfunction "32_32") (pintype "passive"))
      (node (ref "CON2") (pin "34") (pinfunction "34_34") (pintype "passive"))
      (node (ref "CON2") (pin "36") (pinfunction "36_36") (pintype "passive"))
      (node (ref "CON2") (pin "4") (pinfunction "4_4") (pintype "passive"))
      (node (ref "CON2") (pin "6") (pinfunction "6_6") (pintype "passive"))
      (node (ref "CON2") (pin "8") (pinfunction "8_8") (pintype "passive"))
    )
    (net (code "103") (name "TOP-3") (class "Default")
      (node (ref "CON1") (pin "1") (pinfunction "1_1") (pintype "passive"))
      (node (ref "CON1") (pin "11") (pinfunction "11_11") (pintype "passive"))
      (node (ref "CON1") (pin "13") (pinfunction "13_13") (pintype "passive"))
      (node (ref "CON1") (pin "15") (pinfunction "15_15") (pintype "passive"))
      (node (ref "CON1") (pin "17") (pinfunction "17_17") (pintype "passive"))
      (node (ref "CON1") (pin "19") (pinfunction "19_19") (pintype "passive"))
      (node (ref "CON1") (pin "21") (pinfunction "21_21") (pintype "passive"))
      (node (ref "CON1") (pin "23") (pinfunction "23_23") (pintype "passive"))
      (node (ref "CON1") (pin "25") (pinfunction "25_25") (pintype "passive"))
      (node (ref "CON1") (pin "27") (pinfunction "27_27") (pintype "passive"))
      (node (ref "CON1") (pin "29") (pinfunction "29_29") (pintype "passive"))
      (node (ref "CON1") (pin "3") (pinfunction "3_3") (pintype "passive"))
      (node (ref "CON1") (pin "31") (pinfunction "31_31") (pintype "passive"))
      (node (ref "CON1") (pin "33") (pinfunction "33_33") (pintype "passive"))
      (node (ref "CON1") (pin "35") (pinfunction "35_35") (pintype "passive"))
      (node (ref "CON1") (pin "5") (pinfunction "5_5") (pintype "passive"))
      (node (ref "CON1") (pin "7") (pinfunction "7_7") (pintype "passive"))
      (node (ref "CON1") (pin "9") (pinfunction "9_9") (pintype "passive"))
    )
    (net (code "104") (name "TOP-4") (class "Default")
      (node (ref "CON1") (pin "10") (pinfunction "10_10") (pintype "passive"))
      (node (ref "CON1") (pin "12") (pinfunction "12_12") (pintype "passive"))
      (node (ref "CON1") (pin "14") (pinfunction "14_14") (pintype "passive"))
      (node (ref "CON1") (pin "16") (pinfunction "16_16") (pintype "passive"))
      (node (ref "CON1") (pin "18") (pinfunction "18_18") (pintype "passive"))
      (node (ref "CON1") (pin "2") (pinfunction "2_2") (pintype "passive"))
      (node (ref "CON1") (pin "20") (pinfunction "20_20") (pintype "passive"))
      (node (ref "CON1") (pin "22") (pinfunction "22_22") (pintype "passive"))
      (node (ref "CON1") (pin "24") (pinfunction "24_24") (pintype "passive"))
      (node (ref "CON1") (pin "26") (pinfunction "26_26") (pintype "passive"))
      (node (ref "CON1") (pin "28") (pinfunction "28_28") (pintype "passive"))
      (node (ref "CON1") (pin "30") (pinfunction "30_30") (pintype "passive"))
      (node (ref "CON1") (pin "32") (pinfunction "32_32") (pintype "passive"))
      (node (ref "CON1") (pin "34") (pinfunction "34_34") (pintype "passive"))
      (node (ref "CON1") (pin "36") (pinfunction "36_36") (pintype "passive"))
      (node (ref "CON1") (pin "4") (pinfunction "4_4") (pintype "passive"))
      (node (ref "CON1") (pin "6") (pinfunction "6_6") (pintype "passive"))
      (node (ref "CON1") (pin "8") (pinfunction "8_8") (pintype "passive"))
    )
  )
)
